# esp-sme.net
KiCad netlist of a schematic drawn in EAGLE
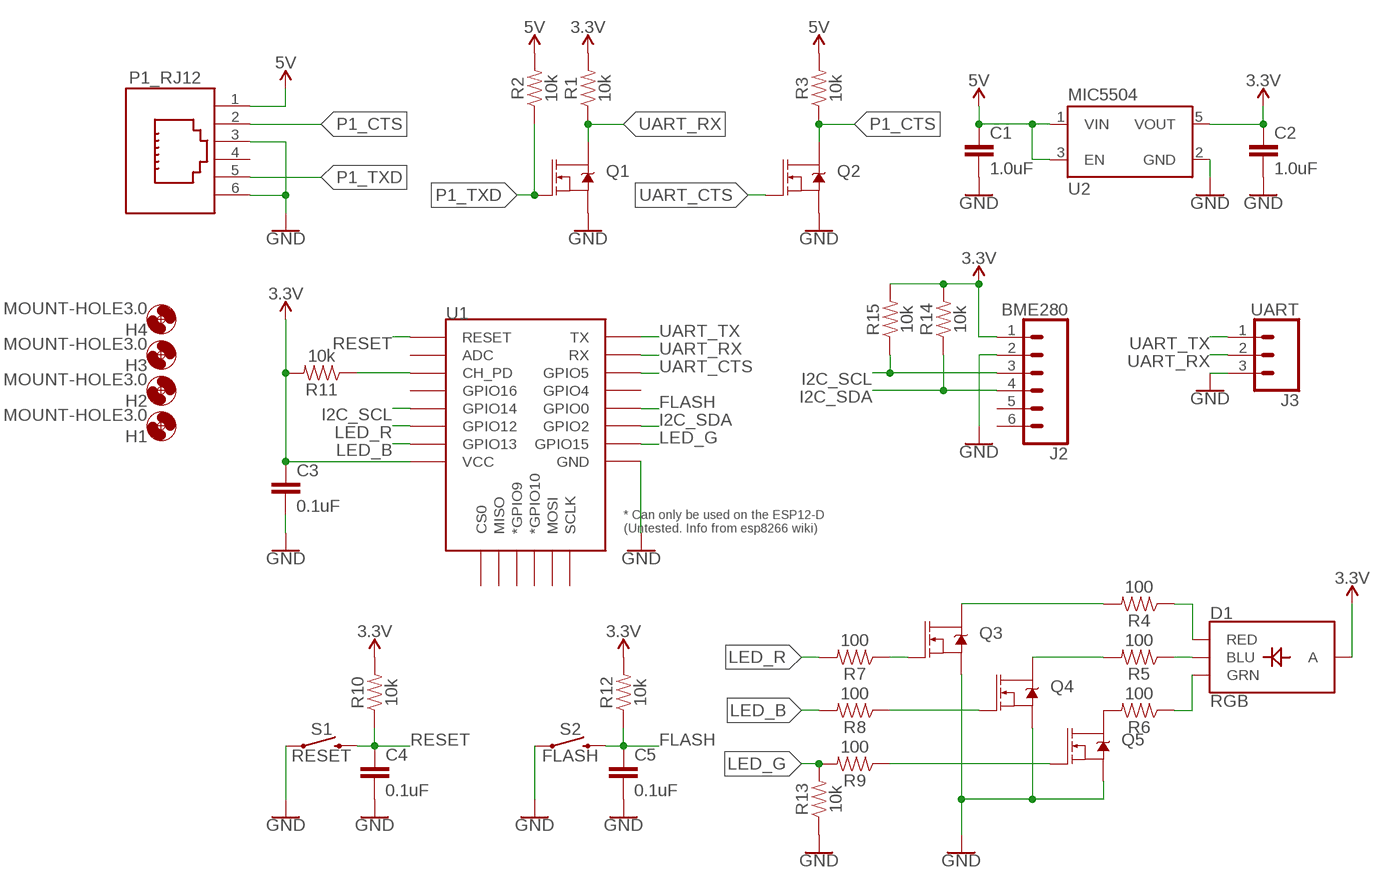
[diagram p0: schematic, sheet 1]

(export (version "E")
  (design (tool "Eeschema 10.0.6"))
  (components
    (comp (ref "C1")
      (value "1.0uF")
      (footprint "eagle-import:0603")
      (libsource (lib "eagle-import") (part "1.0UF-0603-16V-10%"))
    )
    (comp (ref "C2")
      (value "1.0uF")
      (footprint "eagle-import:0603")
      (libsource (lib "eagle-import") (part "1.0UF-0603-16V-10%"))
    )
    (comp (ref "C3")
      (value "0.1uF")
      (footprint "eagle-import:0603")
      (libsource (lib "eagle-import") (part "0.1UF-0603-25V-5%"))
    )
    (comp (ref "C4")
      (value "0.1uF")
      (footprint "eagle-import:0603")
      (libsource (lib "eagle-import") (part "0.1UF-0603-25V-5%"))
    )
    (comp (ref "C5")
      (value "0.1uF")
      (footprint "eagle-import:0603")
      (libsource (lib "eagle-import") (part "0.1UF-0603-25V-5%"))
    )
    (comp (ref "D1")
      (value "RGB")
      (footprint "eagle-import:P-LCC-4-3")
      (libsource (lib "eagle-import") (part "LED-RGB-CAPLCC"))
    )
    (comp (ref "H1")
      (value "MOUNT-HOLE3.0")
      (footprint "eagle-import:3,0")
      (libsource (lib "eagle-import") (part "MOUNT-HOLE3.0"))
    )
    (comp (ref "H2")
      (value "MOUNT-HOLE3.0")
      (footprint "eagle-import:3,0")
      (libsource (lib "eagle-import") (part "MOUNT-HOLE3.0"))
    )
    (comp (ref "H3")
      (value "MOUNT-HOLE3.0")
      (footprint "eagle-import:3,0")
      (libsource (lib "eagle-import") (part "MOUNT-HOLE3.0"))
    )
    (comp (ref "H4")
      (value "MOUNT-HOLE3.0")
      (footprint "eagle-import:3,0")
      (libsource (lib "eagle-import") (part "MOUNT-HOLE3.0"))
    )
    (comp (ref "J2")
      (value "BME280")
      (footprint "eagle-import:1X06")
      (libsource (lib "eagle-import") (part "CONN_06SILK_FEMALE_PTH"))
    )
    (comp (ref "J3")
      (value "UART")
      (footprint "eagle-import:1X03")
      (libsource (lib "eagle-import") (part "CONN_03"))
    )
    (comp (ref "P1_RJ12")
      (value "615006143621")
      (footprint "eagle-import:615006143621")
      (libsource (lib "eagle-import") (part "615006143621"))
    )
    (comp (ref "Q1")
      (value "MOSFET-NCH-AO3404A")
      (footprint "eagle-import:SOT23-3")
      (libsource (lib "eagle-import") (part "MOSFET-NCH-AO3404A"))
    )
    (comp (ref "Q2")
      (value "MOSFET-NCH-AO3404A")
      (footprint "eagle-import:SOT23-3")
      (libsource (lib "eagle-import") (part "MOSFET-NCH-AO3404A"))
    )
    (comp (ref "Q3")
      (value "MOSFET-NCH-AO3404A")
      (footprint "eagle-import:SOT23-3")
      (libsource (lib "eagle-import") (part "MOSFET-NCH-AO3404A"))
    )
    (comp (ref "Q4")
      (value "MOSFET-NCH-AO3404A")
      (footprint "eagle-import:SOT23-3")
      (libsource (lib "eagle-import") (part "MOSFET-NCH-AO3404A"))
    )
    (comp (ref "Q5")
      (value "MOSFET-NCH-AO3404A")
      (footprint "eagle-import:SOT23-3")
      (libsource (lib "eagle-import") (part "MOSFET-NCH-AO3404A"))
    )
    (comp (ref "R1")
      (value "10k")
      (footprint "eagle-import:0603")
      (libsource (lib "eagle-import") (part "10KOHM-0603-1/10W-1%"))
    )
    (comp (ref "R2")
      (value "10k")
      (footprint "eagle-import:0603")
      (libsource (lib "eagle-import") (part "10KOHM-0603-1/10W-1%"))
    )
    (comp (ref "R3")
      (value "10k")
      (footprint "eagle-import:0603")
      (libsource (lib "eagle-import") (part "10KOHM-0603-1/10W-1%"))
    )
    (comp (ref "R4")
      (value "100")
      (footprint "eagle-import:0603")
      (libsource (lib "eagle-import") (part "100OHM-0603-1/10W-1%"))
    )
    (comp (ref "R5")
      (value "100")
      (footprint "eagle-import:0603")
      (libsource (lib "eagle-import") (part "100OHM-0603-1/10W-1%"))
    )
    (comp (ref "R6")
      (value "100")
      (footprint "eagle-import:0603")
      (libsource (lib "eagle-import") (part "100OHM-0603-1/10W-1%"))
    )
    (comp (ref "R7")
      (value "100")
      (footprint "eagle-import:0603")
      (libsource (lib "eagle-import") (part "100OHM-0603-1/10W-1%"))
    )
    (comp (ref "R8")
      (value "100")
      (footprint "eagle-import:0603")
      (libsource (lib "eagle-import") (part "100OHM-0603-1/10W-1%"))
    )
    (comp (ref "R9")
      (value "100")
      (footprint "eagle-import:0603")
      (libsource (lib "eagle-import") (part "100OHM-0603-1/10W-1%"))
    )
    (comp (ref "R10")
      (value "10k")
      (footprint "eagle-import:0603")
      (libsource (lib "eagle-import") (part "10KOHM-0603-1/10W-1%"))
    )
    (comp (ref "R11")
      (value "10k")
      (footprint "eagle-import:0603")
      (libsource (lib "eagle-import") (part "10KOHM-0603-1/10W-1%"))
    )
    (comp (ref "R12")
      (value "10k")
      (footprint "eagle-import:0603")
      (libsource (lib "eagle-import") (part "10KOHM-0603-1/10W-1%"))
    )
    (comp (ref "R13")
      (value "10k")
      (footprint "eagle-import:0603")
      (libsource (lib "eagle-import") (part "10KOHM-0603-1/10W-1%"))
    )
    (comp (ref "R14")
      (value "10k")
      (footprint "eagle-import:0603")
      (libsource (lib "eagle-import") (part "10KOHM-0603-1/10W-1%"))
    )
    (comp (ref "R15")
      (value "10k")
      (footprint "eagle-import:0603")
      (libsource (lib "eagle-import") (part "10KOHM-0603-1/10W-1%"))
    )
    (comp (ref "S1")
      (value "RESET")
      (footprint "eagle-import:TACTILE_SWITCH_SMD_4.6X2.8MM")
      (libsource (lib "eagle-import") (part "MOMENTARY-SWITCH-SPST-SMD-4.6X2.8MM"))
    )
    (comp (ref "S2")
      (value "FLASH")
      (footprint "eagle-import:TACTILE_SWITCH_SMD_4.6X2.8MM")
      (libsource (lib "eagle-import") (part "MOMENTARY-SWITCH-SPST-SMD-4.6X2.8MM"))
    )
    (comp (ref "U1")
      (value "ESP12ESMD")
      (footprint "eagle-import:ESP12E-SMD")
      (libsource (lib "eagle-import") (part "ESP12ESMD"))
    )
    (comp (ref "U2")
      (value "MIC5504")
      (footprint "eagle-import:SOT23-5")
      (libsource (lib "eagle-import") (part "MIC5504"))
    )
  )
  (nets
    (net (code "1") (name "/FLASH") (class "Default")
      (node (ref "C5") (pin "1") (pinfunction "1_1") (pintype "passive"))
      (node (ref "R12") (pin "1") (pinfunction "1_1") (pintype "passive"))
      (node (ref "S2") (pin "3") (pinfunction "2_3") (pintype "passive"))
      (node (ref "S2") (pin "4") (pinfunction "2_4") (pintype "passive"))
      (node (ref "U1") (pin "GPIO0") (pinfunction "GPIO0_GPIO0") (pintype "bidirectional"))
    )
    (net (code "2") (name "/I2C_SCL") (class "Default")
      (node (ref "J2") (pin "3") (pinfunction "3_3") (pintype "passive"))
      (node (ref "R15") (pin "1") (pinfunction "1_1") (pintype "passive"))
      (node (ref "U1") (pin "GPIO14") (pinfunction "GPIO14_GPIO14") (pintype "bidirectional"))
    )
    (net (code "3") (name "/I2C_SDA") (class "Default")
      (node (ref "J2") (pin "4") (pinfunction "4_4") (pintype "passive"))
      (node (ref "R14") (pin "1") (pinfunction "1_1") (pintype "passive"))
      (node (ref "U1") (pin "GPIO2") (pinfunction "GPIO2_GPIO2") (pintype "bidirectional"))
    )
    (net (code "4") (name "/RESET") (class "Default")
      (node (ref "C4") (pin "1") (pinfunction "1_1") (pintype "passive"))
      (node (ref "R10") (pin "1") (pinfunction "1_1") (pintype "passive"))
      (node (ref "S1") (pin "3") (pinfunction "2_3") (pintype "passive"))
      (node (ref "S1") (pin "4") (pinfunction "2_4") (pintype "passive"))
      (node (ref "U1") (pin "RESET") (pinfunction "RESET_RESET") (pintype "bidirectional"))
    )
    (net (code "5") (name "/UART_TX") (class "Default")
      (node (ref "J3") (pin "1") (pinfunction "1_1") (pintype "passive"))
      (node (ref "U1") (pin "TXD0") (pinfunction "TX_TXD0") (pintype "bidirectional"))
    )
    (net (code "6") (name "3.3V") (class "Default")
      (node (ref "C2") (pin "1") (pinfunction "1_1") (pintype "passive"))
      (node (ref "C3") (pin "1") (pinfunction "1_1") (pintype "passive"))
      (node (ref "D1") (pin "4") (pinfunction "A_4") (pintype "bidirectional"))
      (node (ref "J2") (pin "1") (pinfunction "1_1") (pintype "passive"))
      (node (ref "R1") (pin "2") (pinfunction "2_2") (pintype "passive"))
      (node (ref "R10") (pin "2") (pinfunction "2_2") (pintype "passive"))
      (node (ref "R11") (pin "2") (pinfunction "2_2") (pintype "passive"))
      (node (ref "R12") (pin "2") (pinfunction "2_2") (pintype "passive"))
      (node (ref "R14") (pin "2") (pinfunction "2_2") (pintype "passive"))
      (node (ref "R15") (pin "2") (pinfunction "2_2") (pintype "passive"))
      (node (ref "U1") (pin "VCC") (pinfunction "VCC_VCC") (pintype "bidirectional"))
      (node (ref "U2") (pin "5") (pinfunction "VOUT_5") (pintype "bidirectional"))
    )
    (net (code "7") (name "5V") (class "Default")
      (node (ref "C1") (pin "1") (pinfunction "1_1") (pintype "passive"))
      (node (ref "P1_RJ12") (pin "1") (pinfunction "6_1") (pintype "passive"))
      (node (ref "R2") (pin "2") (pinfunction "2_2") (pintype "passive"))
      (node (ref "R3") (pin "2") (pinfunction "2_2") (pintype "passive"))
      (node (ref "U2") (pin "1") (pinfunction "VIN_1") (pintype "bidirectional"))
      (node (ref "U2") (pin "3") (pinfunction "EN_3") (pintype "bidirectional"))
    )
    (net (code "8") (name "GND") (class "Default")
      (node (ref "C1") (pin "2") (pinfunction "2_2") (pintype "passive"))
      (node (ref "C2") (pin "2") (pinfunction "2_2") (pintype "passive"))
      (node (ref "C3") (pin "2") (pinfunction "2_2") (pintype "passive"))
      (node (ref "C4") (pin "2") (pinfunction "2_2") (pintype "passive"))
      (node (ref "C5") (pin "2") (pinfunction "2_2") (pintype "passive"))
      (node (ref "J2") (pin "2") (pinfunction "2_2") (pintype "passive"))
      (node (ref "J3") (pin "3") (pinfunction "3_3") (pintype "passive"))
      (node (ref "P1_RJ12") (pin "3") (pinfunction "4_3") (pintype "passive"))
      (node (ref "P1_RJ12") (pin "6") (pinfunction "1_6") (pintype "passive"))
      (node (ref "Q1") (pin "2") (pinfunction "S_2") (pintype "bidirectional"))
      (node (ref "Q2") (pin "2") (pinfunction "S_2") (pintype "bidirectional"))
      (node (ref "Q3") (pin "2") (pinfunction "S_2") (pintype "bidirectional"))
      (node (ref "Q4") (pin "2") (pinfunction "S_2") (pintype "bidirectional"))
      (node (ref "Q5") (pin "2") (pinfunction "S_2") (pintype "bidirectional"))
      (node (ref "R13") (pin "1") (pinfunction "1_1") (pintype "passive"))
      (node (ref "S1") (pin "1") (pinfunction "1_1") (pintype "passive"))
      (node (ref "S1") (pin "2") (pinfunction "1_2") (pintype "passive"))
      (node (ref "S2") (pin "1") (pinfunction "1_1") (pintype "passive"))
      (node (ref "S2") (pin "2") (pinfunction "1_2") (pintype "passive"))
      (node (ref "U1") (pin "GND") (pinfunction "GND_GND") (pintype "bidirectional"))
      (node (ref "U2") (pin "2") (pinfunction "GND_2") (pintype "bidirectional"))
    )
    (net (code "9") (name "LED_B") (class "Default")
      (node (ref "R8") (pin "2") (pinfunction "2_2") (pintype "passive"))
      (node (ref "U1") (pin "GPIO13") (pinfunction "GPIO13_GPIO13") (pintype "bidirectional"))
    )
    (net (code "10") (name "LED_G") (class "Default")
      (node (ref "R13") (pin "2") (pinfunction "2_2") (pintype "passive"))
      (node (ref "R9") (pin "2") (pinfunction "2_2") (pintype "passive"))
      (node (ref "U1") (pin "GPIO15") (pinfunction "GPIO15_GPIO15") (pintype "bidirectional"))
    )
    (net (code "11") (name "LED_R") (class "Default")
      (node (ref "R7") (pin "2") (pinfunction "2_2") (pintype "passive"))
      (node (ref "U1") (pin "GPIO12") (pinfunction "GPIO12_GPIO12") (pintype "bidirectional"))
    )
    (net (code "12") (name "Net-(D1-BLU)") (class "Default")
      (node (ref "D1") (pin "3") (pinfunction "BLU_3") (pintype "bidirectional"))
      (node (ref "R5") (pin "1") (pinfunction "1_1") (pintype "passive"))
    )
    (net (code "13") (name "Net-(D1-GRN)") (class "Default")
      (node (ref "D1") (pin "2") (pinfunction "GRN_2") (pintype "bidirectional"))
      (node (ref "R6") (pin "1") (pinfunction "1_1") (pintype "passive"))
    )
    (net (code "14") (name "Net-(D1-RED)") (class "Default")
      (node (ref "D1") (pin "1") (pinfunction "RED_1") (pintype "bidirectional"))
      (node (ref "R4") (pin "1") (pinfunction "1_1") (pintype "passive"))
    )
    (net (code "15") (name "Net-(Q3-D)") (class "Default")
      (node (ref "Q3") (pin "3") (pinfunction "D_3") (pintype "bidirectional"))
      (node (ref "R4") (pin "2") (pinfunction "2_2") (pintype "passive"))
    )
    (net (code "16") (name "Net-(Q3-G)") (class "Default")
      (node (ref "Q3") (pin "1") (pinfunction "G_1") (pintype "bidirectional"))
      (node (ref "R7") (pin "1") (pinfunction "1_1") (pintype "passive"))
    )
    (net (code "17") (name "Net-(Q4-D)") (class "Default")
      (node (ref "Q4") (pin "3") (pinfunction "D_3") (pintype "bidirectional"))
      (node (ref "R5") (pin "2") (pinfunction "2_2") (pintype "passive"))
    )
    (net (code "18") (name "Net-(Q4-G)") (class "Default")
      (node (ref "Q4") (pin "1") (pinfunction "G_1") (pintype "bidirectional"))
      (node (ref "R8") (pin "1") (pinfunction "1_1") (pintype "passive"))
    )
    (net (code "19") (name "Net-(Q5-D)") (class "Default")
      (node (ref "Q5") (pin "3") (pinfunction "D_3") (pintype "bidirectional"))
      (node (ref "R6") (pin "2") (pinfunction "2_2") (pintype "passive"))
    )
    (net (code "20") (name "Net-(Q5-G)") (class "Default")
      (node (ref "Q5") (pin "1") (pinfunction "G_1") (pintype "bidirectional"))
      (node (ref "R9") (pin "1") (pinfunction "1_1") (pintype "passive"))
    )
    (net (code "21") (name "Net-(R11-Pad1)") (class "Default")
      (node (ref "R11") (pin "1") (pinfunction "1_1") (pintype "passive"))
      (node (ref "U1") (pin "CH_PD") (pinfunction "CH_PD_CH_PD") (pintype "bidirectional"))
    )
    (net (code "22") (name "P1_CTS") (class "Default")
      (node (ref "P1_RJ12") (pin "2") (pinfunction "5_2") (pintype "passive"))
      (node (ref "Q2") (pin "3") (pinfunction "D_3") (pintype "bidirectional"))
      (node (ref "R3") (pin "1") (pinfunction "1_1") (pintype "passive"))
    )
    (net (code "23") (name "P1_TXD") (class "Default")
      (node (ref "P1_RJ12") (pin "5") (pinfunction "2_5") (pintype "passive"))
      (node (ref "Q1") (pin "1") (pinfunction "G_1") (pintype "bidirectional"))
      (node (ref "R2") (pin "1") (pinfunction "1_1") (pintype "passive"))
    )
    (net (code "24") (name "UART_CTS") (class "Default")
      (node (ref "Q2") (pin "1") (pinfunction "G_1") (pintype "bidirectional"))
      (node (ref "U1") (pin "GPIO5") (pinfunction "GPIO5_GPIO5") (pintype "bidirectional"))
    )
    (net (code "25") (name "UART_RX") (class "Default")
      (node (ref "J3") (pin "2") (pinfunction "2_2") (pintype "passive"))
      (node (ref "Q1") (pin "3") (pinfunction "D_3") (pintype "bidirectional"))
      (node (ref "R1") (pin "1") (pinfunction "1_1") (pintype "passive"))
      (node (ref "U1") (pin "RXD0") (pinfunction "RX_RXD0") (pintype "bidirectional"))
    )
    (net (code "26") (name "unconnected-(J2-Pad5)") (class "Default")
      (node (ref "J2") (pin "5") (pinfunction "5_5") (pintype "passive"))
    )
    (net (code "27") (name "unconnected-(J2-Pad6)") (class "Default")
      (node (ref "J2") (pin "6") (pinfunction "6_6") (pintype "passive"))
    )
    (net (code "28") (name "unconnected-(P1_RJ12-3-Pad4)") (class "Default")
      (node (ref "P1_RJ12") (pin "4") (pinfunction "3_4") (pintype "passive"))
    )
    (net (code "29") (name "unconnected-(U1-*GPIO9-PadGPIO9)") (class "Default")
      (node (ref "U1") (pin "GPIO9") (pinfunction "*GPIO9_GPIO9") (pintype "bidirectional"))
    )
    (net (code "30") (name "unconnected-(U1-*GPIO10-PadGPIO10)") (class "Default")
      (node (ref "U1") (pin "GPIO10") (pinfunction "*GPIO10_GPIO10") (pintype "bidirectional"))
    )
    (net (code "31") (name "unconnected-(U1-PadADC)") (class "Default")
      (node (ref "U1") (pin "ADC") (pinfunction "ADC_ADC") (pintype "bidirectional"))
    )
    (net (code "32") (name "unconnected-(U1-PadCS0)") (class "Default")
      (node (ref "U1") (pin "CS0") (pinfunction "CS0_CS0") (pintype "bidirectional"))
    )
    (net (code "33") (name "unconnected-(U1-PadGPIO4)") (class "Default")
      (node (ref "U1") (pin "GPIO4") (pinfunction "GPIO4_GPIO4") (pintype "bidirectional"))
    )
    (net (code "34") (name "unconnected-(U1-PadGPIO16)") (class "Default")
      (node (ref "U1") (pin "GPIO16") (pinfunction "GPIO16_GPIO16") (pintype "bidirectional"))
    )
    (net (code "35") (name "unconnected-(U1-PadMISO)") (class "Default")
      (node (ref "U1") (pin "MISO") (pinfunction "MISO_MISO") (pintype "bidirectional"))
    )
    (net (code "36") (name "unconnected-(U1-PadMOSI)") (class "Default")
      (node (ref "U1") (pin "MOSI") (pinfunction "MOSI_MOSI") (pintype "bidirectional"))
    )
    (net (code "37") (name "unconnected-(U1-PadSCLK)") (class "Default")
      (node (ref "U1") (pin "SCLK") (pinfunction "SCLK_SCLK") (pintype "bidirectional"))
    )
  )
)
